# keymap.net
KiCad netlist of a schematic drawn in Altium Designer
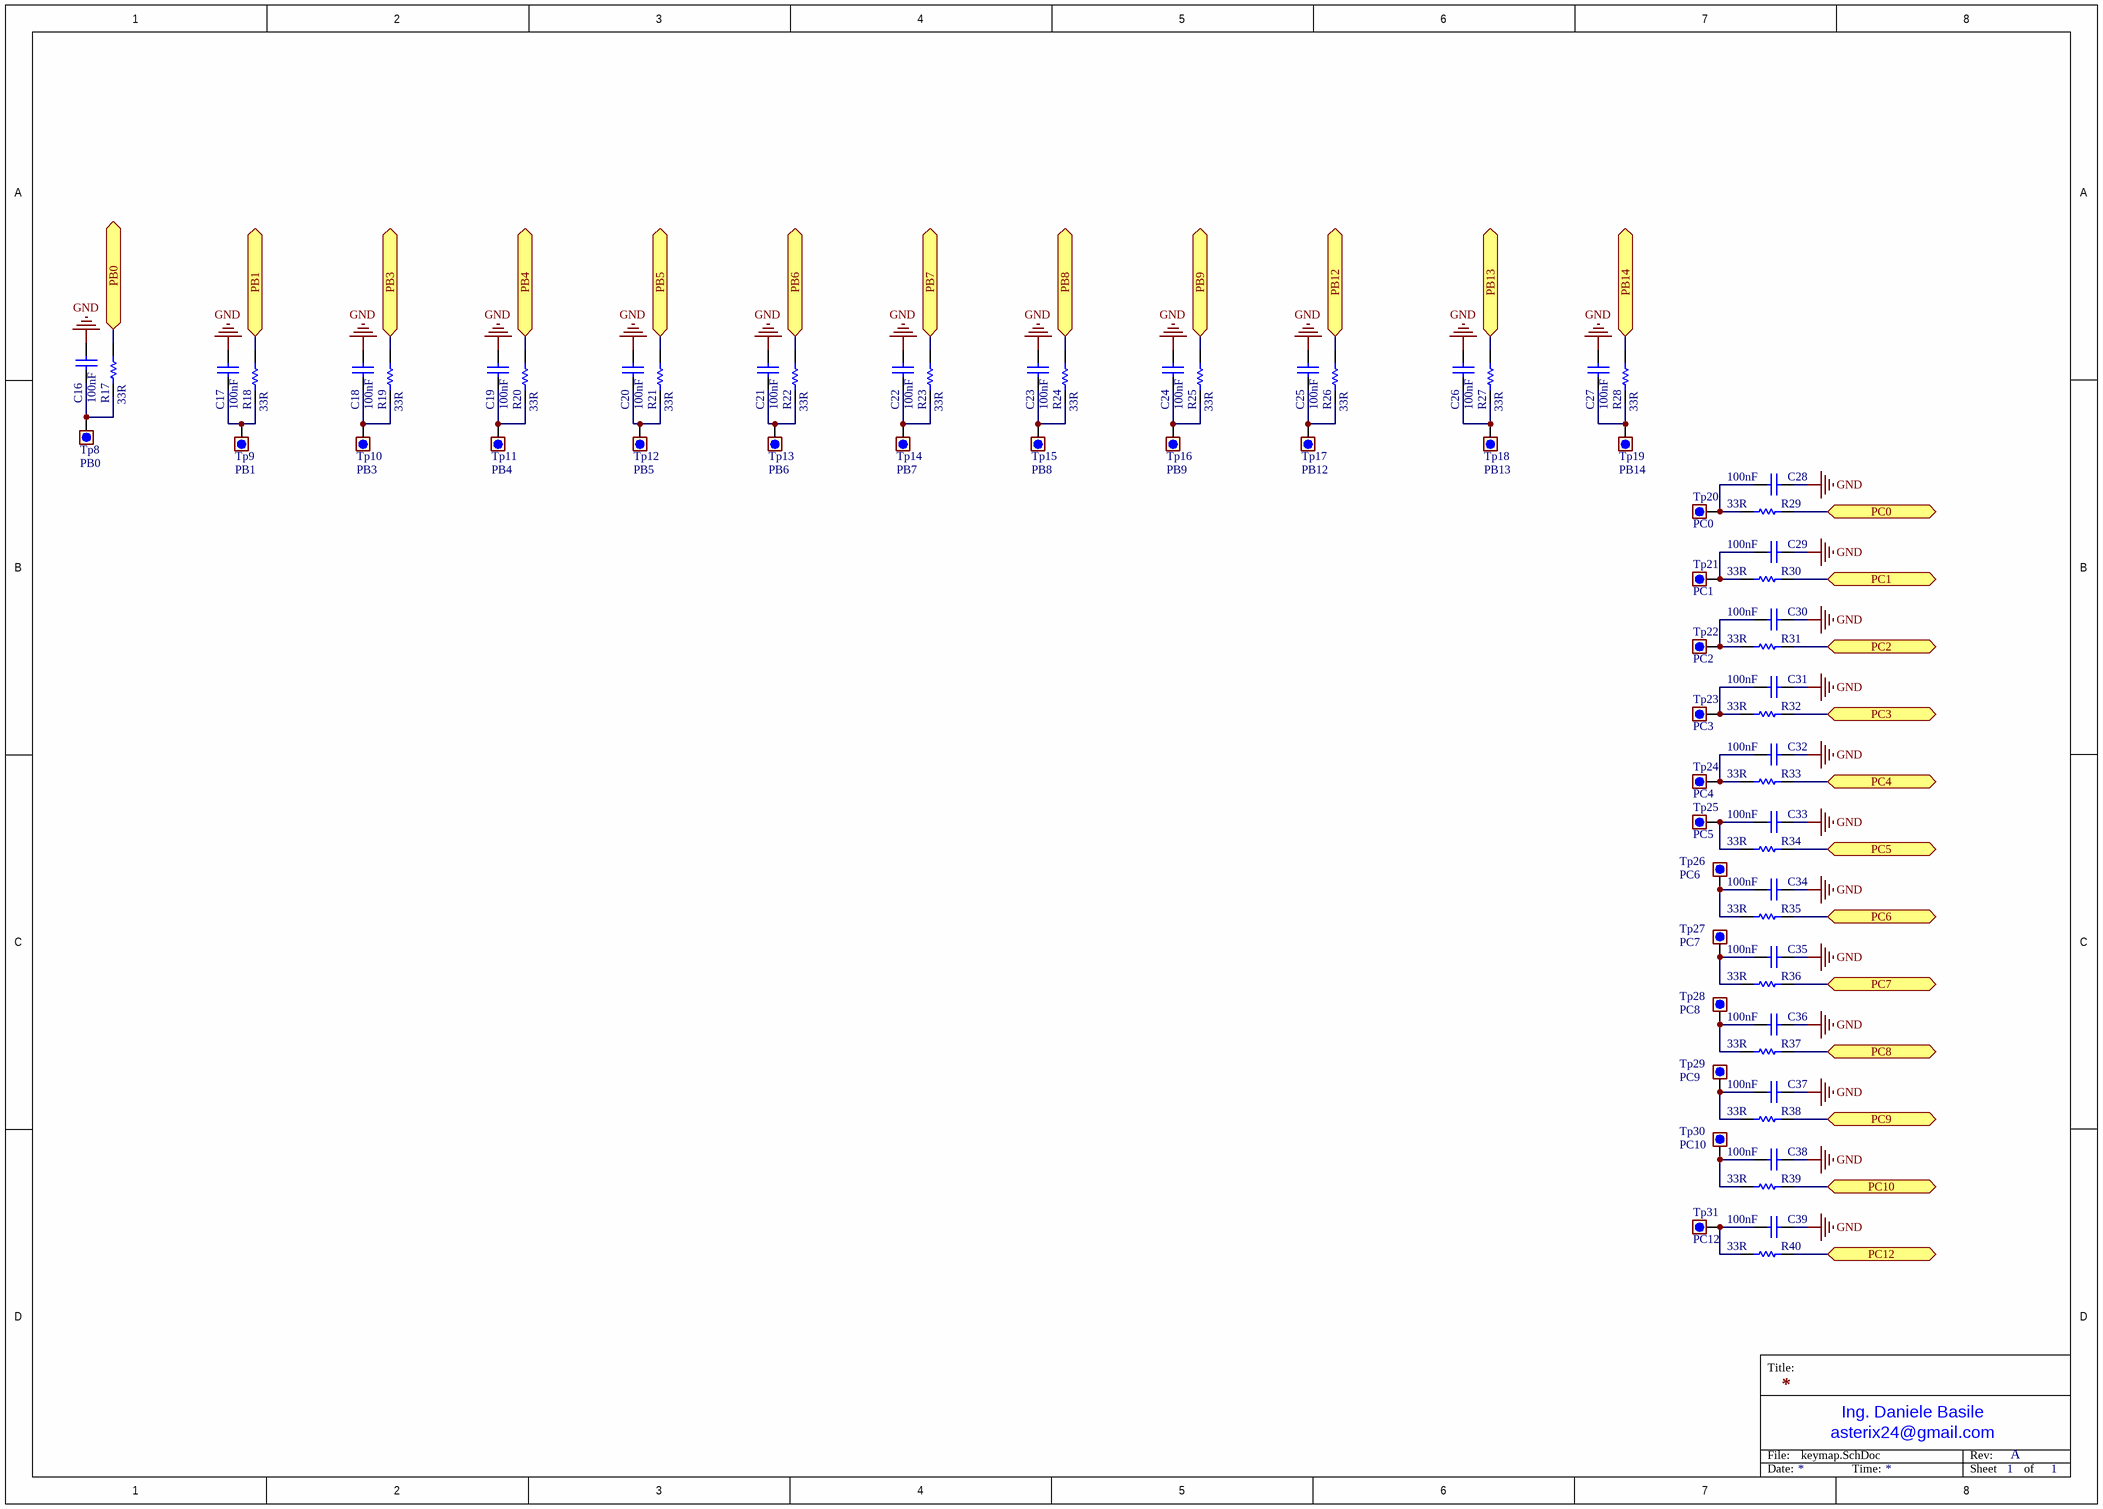
[diagram p0: keymap.SchDoc]

(export (version "E")
  (design (tool "Eeschema 10.0.6"))
  (components
    (comp (ref "C16")
      (value "100nF")
      (footprint "0603_[1608]")
      (description "Ceramic X7R 50V")
      (fields (field (name "PUBLISHER") "Altium Limited"))
      (libsource (lib "DEVELER_Library") (part "Cap"))
    )
    (comp (ref "C17")
      (value "100nF")
      (footprint "0603_[1608]")
      (description "Ceramic X7R 50V")
      (fields (field (name "PUBLISHER") "Altium Limited"))
      (libsource (lib "DEVELER_Library") (part "Cap"))
    )
    (comp (ref "C18")
      (value "100nF")
      (footprint "0603_[1608]")
      (description "Ceramic X7R 50V")
      (fields (field (name "PUBLISHER") "Altium Limited"))
      (libsource (lib "DEVELER_Library") (part "Cap"))
    )
    (comp (ref "C19")
      (value "100nF")
      (footprint "0603_[1608]")
      (description "Ceramic X7R 50V")
      (fields (field (name "PUBLISHER") "Altium Limited"))
      (libsource (lib "DEVELER_Library") (part "Cap"))
    )
    (comp (ref "C20")
      (value "100nF")
      (footprint "0603_[1608]")
      (description "Ceramic X7R 50V")
      (fields (field (name "PUBLISHER") "Altium Limited"))
      (libsource (lib "DEVELER_Library") (part "Cap"))
    )
    (comp (ref "C21")
      (value "100nF")
      (footprint "0603_[1608]")
      (description "Ceramic X7R 50V")
      (fields (field (name "PUBLISHER") "Altium Limited"))
      (libsource (lib "DEVELER_Library") (part "Cap"))
    )
    (comp (ref "C22")
      (value "100nF")
      (footprint "0603_[1608]")
      (description "Ceramic X7R 50V")
      (fields (field (name "PUBLISHER") "Altium Limited"))
      (libsource (lib "DEVELER_Library") (part "Cap"))
    )
    (comp (ref "C23")
      (value "100nF")
      (footprint "0603_[1608]")
      (description "Ceramic X7R 50V")
      (fields (field (name "PUBLISHER") "Altium Limited"))
      (libsource (lib "DEVELER_Library") (part "Cap"))
    )
    (comp (ref "C24")
      (value "100nF")
      (footprint "0603_[1608]")
      (description "Ceramic X7R 50V")
      (fields (field (name "PUBLISHER") "Altium Limited"))
      (libsource (lib "DEVELER_Library") (part "Cap"))
    )
    (comp (ref "C25")
      (value "100nF")
      (footprint "0603_[1608]")
      (description "Ceramic X7R 50V")
      (fields (field (name "PUBLISHER") "Altium Limited"))
      (libsource (lib "DEVELER_Library") (part "Cap"))
    )
    (comp (ref "C26")
      (value "100nF")
      (footprint "0603_[1608]")
      (description "Ceramic X7R 50V")
      (fields (field (name "PUBLISHER") "Altium Limited"))
      (libsource (lib "DEVELER_Library") (part "Cap"))
    )
    (comp (ref "C27")
      (value "100nF")
      (footprint "0603_[1608]")
      (description "Ceramic X7R 50V")
      (fields (field (name "PUBLISHER") "Altium Limited"))
      (libsource (lib "DEVELER_Library") (part "Cap"))
    )
    (comp (ref "C28")
      (value "100nF")
      (footprint "0603_[1608]")
      (description "Ceramic X7R 50V")
      (fields (field (name "PUBLISHER") "Altium Limited"))
      (libsource (lib "DEVELER_Library") (part "Cap"))
    )
    (comp (ref "C29")
      (value "100nF")
      (footprint "0603_[1608]")
      (description "Ceramic X7R 50V")
      (fields (field (name "PUBLISHER") "Altium Limited"))
      (libsource (lib "DEVELER_Library") (part "Cap"))
    )
    (comp (ref "C30")
      (value "100nF")
      (footprint "0603_[1608]")
      (description "Ceramic X7R 50V")
      (fields (field (name "PUBLISHER") "Altium Limited"))
      (libsource (lib "DEVELER_Library") (part "Cap"))
    )
    (comp (ref "C31")
      (value "100nF")
      (footprint "0603_[1608]")
      (description "Ceramic X7R 50V")
      (fields (field (name "PUBLISHER") "Altium Limited"))
      (libsource (lib "DEVELER_Library") (part "Cap"))
    )
    (comp (ref "C32")
      (value "100nF")
      (footprint "0603_[1608]")
      (description "Ceramic X7R 50V")
      (fields (field (name "PUBLISHER") "Altium Limited"))
      (libsource (lib "DEVELER_Library") (part "Cap"))
    )
    (comp (ref "C33")
      (value "100nF")
      (footprint "0603_[1608]")
      (description "Ceramic X7R 50V")
      (fields (field (name "PUBLISHER") "Altium Limited"))
      (libsource (lib "DEVELER_Library") (part "Cap"))
    )
    (comp (ref "C34")
      (value "100nF")
      (footprint "0603_[1608]")
      (description "Ceramic X7R 50V")
      (fields (field (name "PUBLISHER") "Altium Limited"))
      (libsource (lib "DEVELER_Library") (part "Cap"))
    )
    (comp (ref "C35")
      (value "100nF")
      (footprint "0603_[1608]")
      (description "Ceramic X7R 50V")
      (fields (field (name "PUBLISHER") "Altium Limited"))
      (libsource (lib "DEVELER_Library") (part "Cap"))
    )
    (comp (ref "C36")
      (value "100nF")
      (footprint "0603_[1608]")
      (description "Ceramic X7R 50V")
      (fields (field (name "PUBLISHER") "Altium Limited"))
      (libsource (lib "DEVELER_Library") (part "Cap"))
    )
    (comp (ref "C37")
      (value "100nF")
      (footprint "0603_[1608]")
      (description "Ceramic X7R 50V")
      (fields (field (name "PUBLISHER") "Altium Limited"))
      (libsource (lib "DEVELER_Library") (part "Cap"))
    )
    (comp (ref "C38")
      (value "100nF")
      (footprint "0603_[1608]")
      (description "Ceramic X7R 50V")
      (fields (field (name "PUBLISHER") "Altium Limited"))
      (libsource (lib "DEVELER_Library") (part "Cap"))
    )
    (comp (ref "C39")
      (value "100nF")
      (footprint "0603_[1608]")
      (description "Ceramic X7R 50V")
      (fields (field (name "PUBLISHER") "Altium Limited"))
      (libsource (lib "DEVELER_Library") (part "Cap"))
    )
    (comp (ref "R17")
      (value "33R")
      (footprint "0603_[1608]")
      (description "Resistor")
      (fields (field (name "PUBLISHER") "Altium Limited"))
      (libsource (lib "simboli") (part "Res1"))
    )
    (comp (ref "R18")
      (value "33R")
      (footprint "0603_[1608]")
      (description "Resistor")
      (fields (field (name "PUBLISHER") "Altium Limited"))
      (libsource (lib "simboli") (part "Res1"))
    )
    (comp (ref "R19")
      (value "33R")
      (footprint "0603_[1608]")
      (description "Resistor")
      (fields (field (name "PUBLISHER") "Altium Limited"))
      (libsource (lib "simboli") (part "Res1"))
    )
    (comp (ref "R20")
      (value "33R")
      (footprint "0603_[1608]")
      (description "Resistor")
      (fields (field (name "PUBLISHER") "Altium Limited"))
      (libsource (lib "simboli") (part "Res1"))
    )
    (comp (ref "R21")
      (value "33R")
      (footprint "0603_[1608]")
      (description "Resistor")
      (fields (field (name "PUBLISHER") "Altium Limited"))
      (libsource (lib "simboli") (part "Res1"))
    )
    (comp (ref "R22")
      (value "33R")
      (footprint "0603_[1608]")
      (description "Resistor")
      (fields (field (name "PUBLISHER") "Altium Limited"))
      (libsource (lib "simboli") (part "Res1"))
    )
    (comp (ref "R23")
      (value "33R")
      (footprint "0603_[1608]")
      (description "Resistor")
      (fields (field (name "PUBLISHER") "Altium Limited"))
      (libsource (lib "simboli") (part "Res1"))
    )
    (comp (ref "R24")
      (value "33R")
      (footprint "0603_[1608]")
      (description "Resistor")
      (fields (field (name "PUBLISHER") "Altium Limited"))
      (libsource (lib "simboli") (part "Res1"))
    )
    (comp (ref "R25")
      (value "33R")
      (footprint "0603_[1608]")
      (description "Resistor")
      (fields (field (name "PUBLISHER") "Altium Limited"))
      (libsource (lib "simboli") (part "Res1"))
    )
    (comp (ref "R26")
      (value "33R")
      (footprint "0603_[1608]")
      (description "Resistor")
      (fields (field (name "PUBLISHER") "Altium Limited"))
      (libsource (lib "simboli") (part "Res1"))
    )
    (comp (ref "R27")
      (value "33R")
      (footprint "0603_[1608]")
      (description "Resistor")
      (fields (field (name "PUBLISHER") "Altium Limited"))
      (libsource (lib "simboli") (part "Res1"))
    )
    (comp (ref "R28")
      (value "33R")
      (footprint "0603_[1608]")
      (description "Resistor")
      (fields (field (name "PUBLISHER") "Altium Limited"))
      (libsource (lib "simboli") (part "Res1"))
    )
    (comp (ref "R29")
      (value "33R")
      (footprint "0603_[1608]")
      (description "Resistor")
      (fields (field (name "PUBLISHER") "Altium Limited"))
      (libsource (lib "simboli") (part "Res1"))
    )
    (comp (ref "R30")
      (value "33R")
      (footprint "0603_[1608]")
      (description "Resistor")
      (fields (field (name "PUBLISHER") "Altium Limited"))
      (libsource (lib "simboli") (part "Res1"))
    )
    (comp (ref "R31")
      (value "33R")
      (footprint "0603_[1608]")
      (description "Resistor")
      (fields (field (name "PUBLISHER") "Altium Limited"))
      (libsource (lib "simboli") (part "Res1"))
    )
    (comp (ref "R32")
      (value "33R")
      (footprint "0603_[1608]")
      (description "Resistor")
      (fields (field (name "PUBLISHER") "Altium Limited"))
      (libsource (lib "simboli") (part "Res1"))
    )
    (comp (ref "R33")
      (value "33R")
      (footprint "0603_[1608]")
      (description "Resistor")
      (fields (field (name "PUBLISHER") "Altium Limited"))
      (libsource (lib "simboli") (part "Res1"))
    )
    (comp (ref "R34")
      (value "33R")
      (footprint "0603_[1608]")
      (description "Resistor")
      (fields (field (name "PUBLISHER") "Altium Limited"))
      (libsource (lib "simboli") (part "Res1"))
    )
    (comp (ref "R35")
      (value "33R")
      (footprint "0603_[1608]")
      (description "Resistor")
      (fields (field (name "PUBLISHER") "Altium Limited"))
      (libsource (lib "simboli") (part "Res1"))
    )
    (comp (ref "R36")
      (value "33R")
      (footprint "0603_[1608]")
      (description "Resistor")
      (fields (field (name "PUBLISHER") "Altium Limited"))
      (libsource (lib "simboli") (part "Res1"))
    )
    (comp (ref "R37")
      (value "33R")
      (footprint "0603_[1608]")
      (description "Resistor")
      (fields (field (name "PUBLISHER") "Altium Limited"))
      (libsource (lib "simboli") (part "Res1"))
    )
    (comp (ref "R38")
      (value "33R")
      (footprint "0603_[1608]")
      (description "Resistor")
      (fields (field (name "PUBLISHER") "Altium Limited"))
      (libsource (lib "simboli") (part "Res1"))
    )
    (comp (ref "R39")
      (value "33R")
      (footprint "0603_[1608]")
      (description "Resistor")
      (fields (field (name "PUBLISHER") "Altium Limited"))
      (libsource (lib "simboli") (part "Res1"))
    )
    (comp (ref "R40")
      (value "33R")
      (footprint "0603_[1608]")
      (description "Resistor")
      (fields (field (name "PUBLISHER") "Altium Limited"))
      (libsource (lib "simboli") (part "Res1"))
    )
    (comp (ref "Tp8")
      (value "PB0")
      (footprint "TEST_POINT_THD_D1.6mm_oval")
      (description "Test point")
      (libsource (lib "DEVELER_Library") (part "Test_point"))
    )
    (comp (ref "Tp9")
      (value "PB1")
      (footprint "TEST_POINT_THD_D1.6mm_oval")
      (description "Test point")
      (libsource (lib "DEVELER_Library") (part "Test_point"))
    )
    (comp (ref "Tp10")
      (value "PB3")
      (footprint "TEST_POINT_THD_D1.6mm_oval")
      (description "Test point")
      (libsource (lib "DEVELER_Library") (part "Test_point"))
    )
    (comp (ref "Tp11")
      (value "PB4")
      (footprint "TEST_POINT_THD_D1.6mm_oval")
      (description "Test point")
      (libsource (lib "DEVELER_Library") (part "Test_point"))
    )
    (comp (ref "Tp12")
      (value "PB5")
      (footprint "TEST_POINT_THD_D1.6mm_oval")
      (description "Test point")
      (libsource (lib "DEVELER_Library") (part "Test_point"))
    )
    (comp (ref "Tp13")
      (value "PB6")
      (footprint "TEST_POINT_THD_D1.6mm_oval")
      (description "Test point")
      (libsource (lib "DEVELER_Library") (part "Test_point"))
    )
    (comp (ref "Tp14")
      (value "PB7")
      (footprint "TEST_POINT_THD_D1.6mm_oval")
      (description "Test point")
      (libsource (lib "DEVELER_Library") (part "Test_point"))
    )
    (comp (ref "Tp15")
      (value "PB8")
      (footprint "TEST_POINT_THD_D1.6mm_oval")
      (description "Test point")
      (libsource (lib "DEVELER_Library") (part "Test_point"))
    )
    (comp (ref "Tp16")
      (value "PB9")
      (footprint "TEST_POINT_THD_D1.6mm_oval")
      (description "Test point")
      (libsource (lib "DEVELER_Library") (part "Test_point"))
    )
    (comp (ref "Tp17")
      (value "PB12")
      (footprint "TEST_POINT_THD_D1.6mm_oval")
      (description "Test point")
      (libsource (lib "DEVELER_Library") (part "Test_point"))
    )
    (comp (ref "Tp18")
      (value "PB13")
      (footprint "TEST_POINT_THD_D1.6mm_oval")
      (description "Test point")
      (libsource (lib "DEVELER_Library") (part "Test_point"))
    )
    (comp (ref "Tp19")
      (value "PB14")
      (footprint "TEST_POINT_THD_D1.6mm_oval")
      (description "Test point")
      (libsource (lib "DEVELER_Library") (part "Test_point"))
    )
    (comp (ref "Tp20")
      (value "PC0")
      (footprint "TEST_POINT_THD_D1.6mm_oval")
      (description "Test point")
      (libsource (lib "") (part "Test_point_1"))
    )
    (comp (ref "Tp21")
      (value "PC1")
      (footprint "TEST_POINT_THD_D1.6mm_oval")
      (description "Test point")
      (libsource (lib "") (part "Test_point_1"))
    )
    (comp (ref "Tp22")
      (value "PC2")
      (footprint "TEST_POINT_THD_D1.6mm_oval")
      (description "Test point")
      (libsource (lib "") (part "Test_point_1"))
    )
    (comp (ref "Tp23")
      (value "PC3")
      (footprint "TEST_POINT_THD_D1.6mm_oval")
      (description "Test point")
      (libsource (lib "") (part "Test_point_1"))
    )
    (comp (ref "Tp24")
      (value "PC4")
      (footprint "TEST_POINT_THD_D1.6mm_oval")
      (description "Test point")
      (libsource (lib "") (part "Test_point_1"))
    )
    (comp (ref "Tp25")
      (value "PC5")
      (footprint "TEST_POINT_THD_D1.6mm_oval")
      (description "Test point")
      (libsource (lib "") (part "Test_point_1"))
    )
    (comp (ref "Tp26")
      (value "PC6")
      (footprint "TEST_POINT_THD_D1.6mm_oval")
      (description "Test point")
      (libsource (lib "") (part "Test_point_2"))
    )
    (comp (ref "Tp27")
      (value "PC7")
      (footprint "TEST_POINT_THD_D1.6mm_oval")
      (description "Test point")
      (libsource (lib "") (part "Test_point_2"))
    )
    (comp (ref "Tp28")
      (value "PC8")
      (footprint "TEST_POINT_THD_D1.6mm_oval")
      (description "Test point")
      (libsource (lib "") (part "Test_point_2"))
    )
    (comp (ref "Tp29")
      (value "PC9")
      (footprint "TEST_POINT_THD_D1.6mm_oval")
      (description "Test point")
      (libsource (lib "") (part "Test_point_2"))
    )
    (comp (ref "Tp30")
      (value "PC10")
      (footprint "TEST_POINT_THD_D1.6mm_oval")
      (description "Test point")
      (libsource (lib "") (part "Test_point_2"))
    )
    (comp (ref "Tp31")
      (value "PC12")
      (footprint "TEST_POINT_THD_D1.6mm_oval")
      (description "Test point")
      (libsource (lib "") (part "Test_point_1"))
    )
  )
  (nets
    (net (code "1") (name "/PB0") (class "Default")
      (node (ref "R17") (pin "2") (pinfunction "2_2") (pintype "passive"))
    )
    (net (code "2") (name "/PB1") (class "Default")
      (node (ref "R18") (pin "2") (pinfunction "2_2") (pintype "passive"))
    )
    (net (code "3") (name "/PB3") (class "Default")
      (node (ref "R19") (pin "2") (pinfunction "2_2") (pintype "passive"))
    )
    (net (code "4") (name "/PB4") (class "Default")
      (node (ref "R20") (pin "2") (pinfunction "2_2") (pintype "passive"))
    )
    (net (code "5") (name "/PB5") (class "Default")
      (node (ref "R21") (pin "2") (pinfunction "2_2") (pintype "passive"))
    )
    (net (code "6") (name "/PB6") (class "Default")
      (node (ref "R22") (pin "2") (pinfunction "2_2") (pintype "passive"))
    )
    (net (code "7") (name "/PB7") (class "Default")
      (node (ref "R23") (pin "2") (pinfunction "2_2") (pintype "passive"))
    )
    (net (code "8") (name "/PB8") (class "Default")
      (node (ref "R24") (pin "2") (pinfunction "2_2") (pintype "passive"))
    )
    (net (code "9") (name "/PB9") (class "Default")
      (node (ref "R25") (pin "2") (pinfunction "2_2") (pintype "passive"))
    )
    (net (code "10") (name "/PB12") (class "Default")
      (node (ref "R26") (pin "2") (pinfunction "2_2") (pintype "passive"))
    )
    (net (code "11") (name "/PB13") (class "Default")
      (node (ref "R27") (pin "2") (pinfunction "2_2") (pintype "passive"))
    )
    (net (code "12") (name "/PB14") (class "Default")
      (node (ref "R28") (pin "2") (pinfunction "2_2") (pintype "passive"))
    )
    (net (code "13") (name "/PC0") (class "Default")
      (node (ref "R29") (pin "2") (pinfunction "2_2") (pintype "passive"))
    )
    (net (code "14") (name "/PC1") (class "Default")
      (node (ref "R30") (pin "2") (pinfunction "2_2") (pintype "passive"))
    )
    (net (code "15") (name "/PC2") (class "Default")
      (node (ref "R31") (pin "2") (pinfunction "2_2") (pintype "passive"))
    )
    (net (code "16") (name "/PC3") (class "Default")
      (node (ref "R32") (pin "2") (pinfunction "2_2") (pintype "passive"))
    )
    (net (code "17") (name "/PC4") (class "Default")
      (node (ref "R33") (pin "2") (pinfunction "2_2") (pintype "passive"))
    )
    (net (code "18") (name "/PC5") (class "Default")
      (node (ref "R34") (pin "2") (pinfunction "2_2") (pintype "passive"))
    )
    (net (code "19") (name "/PC6") (class "Default")
      (node (ref "R35") (pin "2") (pinfunction "2_2") (pintype "passive"))
    )
    (net (code "20") (name "/PC7") (class "Default")
      (node (ref "R36") (pin "2") (pinfunction "2_2") (pintype "passive"))
    )
    (net (code "21") (name "/PC8") (class "Default")
      (node (ref "R37") (pin "2") (pinfunction "2_2") (pintype "passive"))
    )
    (net (code "22") (name "/PC9") (class "Default")
      (node (ref "R38") (pin "2") (pinfunction "2_2") (pintype "passive"))
    )
    (net (code "23") (name "/PC10") (class "Default")
      (node (ref "R39") (pin "2") (pinfunction "2_2") (pintype "passive"))
    )
    (net (code "24") (name "/PC12") (class "Default")
      (node (ref "R40") (pin "2") (pinfunction "2_2") (pintype "passive"))
    )
    (net (code "25") (name "GND") (class "Default")
      (node (ref "C16") (pin "2") (pinfunction "2_2") (pintype "passive"))
      (node (ref "C17") (pin "2") (pinfunction "2_2") (pintype "passive"))
      (node (ref "C18") (pin "2") (pinfunction "2_2") (pintype "passive"))
      (node (ref "C19") (pin "2") (pinfunction "2_2") (pintype "passive"))
      (node (ref "C20") (pin "2") (pinfunction "2_2") (pintype "passive"))
      (node (ref "C21") (pin "2") (pinfunction "2_2") (pintype "passive"))
      (node (ref "C22") (pin "2") (pinfunction "2_2") (pintype "passive"))
      (node (ref "C23") (pin "2") (pinfunction "2_2") (pintype "passive"))
      (node (ref "C24") (pin "2") (pinfunction "2_2") (pintype "passive"))
      (node (ref "C25") (pin "2") (pinfunction "2_2") (pintype "passive"))
      (node (ref "C26") (pin "2") (pinfunction "2_2") (pintype "passive"))
      (node (ref "C27") (pin "2") (pinfunction "2_2") (pintype "passive"))
      (node (ref "C28") (pin "2") (pinfunction "2_2") (pintype "passive"))
      (node (ref "C29") (pin "2") (pinfunction "2_2") (pintype "passive"))
      (node (ref "C30") (pin "2") (pinfunction "2_2") (pintype "passive"))
      (node (ref "C31") (pin "2") (pinfunction "2_2") (pintype "passive"))
      (node (ref "C32") (pin "2") (pinfunction "2_2") (pintype "passive"))
      (node (ref "C33") (pin "2") (pinfunction "2_2") (pintype "passive"))
      (node (ref "C34") (pin "2") (pinfunction "2_2") (pintype "passive"))
      (node (ref "C35") (pin "2") (pinfunction "2_2") (pintype "passive"))
      (node (ref "C36") (pin "2") (pinfunction "2_2") (pintype "passive"))
      (node (ref "C37") (pin "2") (pinfunction "2_2") (pintype "passive"))
      (node (ref "C38") (pin "2") (pinfunction "2_2") (pintype "passive"))
      (node (ref "C39") (pin "2") (pinfunction "2_2") (pintype "passive"))
    )
    (net (code "26") (name "Net-(C16-Pad1)") (class "Default")
      (node (ref "C16") (pin "1") (pinfunction "1_1") (pintype "passive"))
      (node (ref "R17") (pin "1") (pinfunction "1_1") (pintype "passive"))
      (node (ref "Tp8") (pin "1") (pinfunction "1_1") (pintype "passive"))
    )
    (net (code "27") (name "Net-(C17-Pad1)") (class "Default")
      (node (ref "C17") (pin "1") (pinfunction "1_1") (pintype "passive"))
      (node (ref "R18") (pin "1") (pinfunction "1_1") (pintype "passive"))
      (node (ref "Tp9") (pin "1") (pinfunction "1_1") (pintype "passive"))
    )
    (net (code "28") (name "Net-(C18-Pad1)") (class "Default")
      (node (ref "C18") (pin "1") (pinfunction "1_1") (pintype "passive"))
      (node (ref "R19") (pin "1") (pinfunction "1_1") (pintype "passive"))
      (node (ref "Tp10") (pin "1") (pinfunction "1_1") (pintype "passive"))
    )
    (net (code "29") (name "Net-(C19-Pad1)") (class "Default")
      (node (ref "C19") (pin "1") (pinfunction "1_1") (pintype "passive"))
      (node (ref "R20") (pin "1") (pinfunction "1_1") (pintype "passive"))
      (node (ref "Tp11") (pin "1") (pinfunction "1_1") (pintype "passive"))
    )
    (net (code "30") (name "Net-(C20-Pad1)") (class "Default")
      (node (ref "C20") (pin "1") (pinfunction "1_1") (pintype "passive"))
      (node (ref "R21") (pin "1") (pinfunction "1_1") (pintype "passive"))
      (node (ref "Tp12") (pin "1") (pinfunction "1_1") (pintype "passive"))
    )
    (net (code "31") (name "Net-(C21-Pad1)") (class "Default")
      (node (ref "C21") (pin "1") (pinfunction "1_1") (pintype "passive"))
      (node (ref "R22") (pin "1") (pinfunction "1_1") (pintype "passive"))
      (node (ref "Tp13") (pin "1") (pinfunction "1_1") (pintype "passive"))
    )
    (net (code "32") (name "Net-(C22-Pad1)") (class "Default")
      (node (ref "C22") (pin "1") (pinfunction "1_1") (pintype "passive"))
      (node (ref "R23") (pin "1") (pinfunction "1_1") (pintype "passive"))
      (node (ref "Tp14") (pin "1") (pinfunction "1_1") (pintype "passive"))
    )
    (net (code "33") (name "Net-(C23-Pad1)") (class "Default")
      (node (ref "C23") (pin "1") (pinfunction "1_1") (pintype "passive"))
      (node (ref "R24") (pin "1") (pinfunction "1_1") (pintype "passive"))
      (node (ref "Tp15") (pin "1") (pinfunction "1_1") (pintype "passive"))
    )
    (net (code "34") (name "Net-(C24-Pad1)") (class "Default")
      (node (ref "C24") (pin "1") (pinfunction "1_1") (pintype "passive"))
      (node (ref "R25") (pin "1") (pinfunction "1_1") (pintype "passive"))
      (node (ref "Tp16") (pin "1") (pinfunction "1_1") (pintype "passive"))
    )
    (net (code "35") (name "Net-(C25-Pad1)") (class "Default")
      (node (ref "C25") (pin "1") (pinfunction "1_1") (pintype "passive"))
      (node (ref "R26") (pin "1") (pinfunction "1_1") (pintype "passive"))
      (node (ref "Tp17") (pin "1") (pinfunction "1_1") (pintype "passive"))
    )
    (net (code "36") (name "Net-(C26-Pad1)") (class "Default")
      (node (ref "C26") (pin "1") (pinfunction "1_1") (pintype "passive"))
      (node (ref "R27") (pin "1") (pinfunction "1_1") (pintype "passive"))
      (node (ref "Tp18") (pin "1") (pinfunction "1_1") (pintype "passive"))
    )
    (net (code "37") (name "Net-(C27-Pad1)") (class "Default")
      (node (ref "C27") (pin "1") (pinfunction "1_1") (pintype "passive"))
      (node (ref "R28") (pin "1") (pinfunction "1_1") (pintype "passive"))
      (node (ref "Tp19") (pin "1") (pinfunction "1_1") (pintype "passive"))
    )
    (net (code "38") (name "Net-(C28-Pad1)") (class "Default")
      (node (ref "C28") (pin "1") (pinfunction "1_1") (pintype "passive"))
      (node (ref "R29") (pin "1") (pinfunction "1_1") (pintype "passive"))
      (node (ref "Tp20") (pin "1") (pinfunction "1_1") (pintype "passive"))
    )
    (net (code "39") (name "Net-(C29-Pad1)") (class "Default")
      (node (ref "C29") (pin "1") (pinfunction "1_1") (pintype "passive"))
      (node (ref "R30") (pin "1") (pinfunction "1_1") (pintype "passive"))
      (node (ref "Tp21") (pin "1") (pinfunction "1_1") (pintype "passive"))
    )
    (net (code "40") (name "Net-(C30-Pad1)") (class "Default")
      (node (ref "C30") (pin "1") (pinfunction "1_1") (pintype "passive"))
      (node (ref "R31") (pin "1") (pinfunction "1_1") (pintype "passive"))
      (node (ref "Tp22") (pin "1") (pinfunction "1_1") (pintype "passive"))
    )
    (net (code "41") (name "Net-(C31-Pad1)") (class "Default")
      (node (ref "C31") (pin "1") (pinfunction "1_1") (pintype "passive"))
      (node (ref "R32") (pin "1") (pinfunction "1_1") (pintype "passive"))
      (node (ref "Tp23") (pin "1") (pinfunction "1_1") (pintype "passive"))
    )
    (net (code "42") (name "Net-(C32-Pad1)") (class "Default")
      (node (ref "C32") (pin "1") (pinfunction "1_1") (pintype "passive"))
      (node (ref "R33") (pin "1") (pinfunction "1_1") (pintype "passive"))
      (node (ref "Tp24") (pin "1") (pinfunction "1_1") (pintype "passive"))
    )
    (net (code "43") (name "Net-(C33-Pad1)") (class "Default")
      (node (ref "C33") (pin "1") (pinfunction "1_1") (pintype "passive"))
      (node (ref "R34") (pin "1") (pinfunction "1_1") (pintype "passive"))
      (node (ref "Tp25") (pin "1") (pinfunction "1_1") (pintype "passive"))
    )
    (net (code "44") (name "Net-(C34-Pad1)") (class "Default")
      (node (ref "C34") (pin "1") (pinfunction "1_1") (pintype "passive"))
      (node (ref "R35") (pin "1") (pinfunction "1_1") (pintype "passive"))
      (node (ref "Tp26") (pin "1") (pinfunction "1_1") (pintype "passive"))
    )
    (net (code "45") (name "Net-(C35-Pad1)") (class "Default")
      (node (ref "C35") (pin "1") (pinfunction "1_1") (pintype "passive"))
      (node (ref "R36") (pin "1") (pinfunction "1_1") (pintype "passive"))
      (node (ref "Tp27") (pin "1") (pinfunction "1_1") (pintype "passive"))
    )
    (net (code "46") (name "Net-(C36-Pad1)") (class "Default")
      (node (ref "C36") (pin "1") (pinfunction "1_1") (pintype "passive"))
      (node (ref "R37") (pin "1") (pinfunction "1_1") (pintype "passive"))
      (node (ref "Tp28") (pin "1") (pinfunction "1_1") (pintype "passive"))
    )
    (net (code "47") (name "Net-(C37-Pad1)") (class "Default")
      (node (ref "C37") (pin "1") (pinfunction "1_1") (pintype "passive"))
      (node (ref "R38") (pin "1") (pinfunction "1_1") (pintype "passive"))
      (node (ref "Tp29") (pin "1") (pinfunction "1_1") (pintype "passive"))
    )
    (net (code "48") (name "Net-(C38-Pad1)") (class "Default")
      (node (ref "C38") (pin "1") (pinfunction "1_1") (pintype "passive"))
      (node (ref "R39") (pin "1") (pinfunction "1_1") (pintype "passive"))
      (node (ref "Tp30") (pin "1") (pinfunction "1_1") (pintype "passive"))
    )
    (net (code "49") (name "Net-(C39-Pad1)") (class "Default")
      (node (ref "C39") (pin "1") (pinfunction "1_1") (pintype "passive"))
      (node (ref "R40") (pin "1") (pinfunction "1_1") (pintype "passive"))
      (node (ref "Tp31") (pin "1") (pinfunction "1_1") (pintype "passive"))
    )
  )
)
